# schematic.net
KiCad netlist of a schematic drawn in Altium Designer
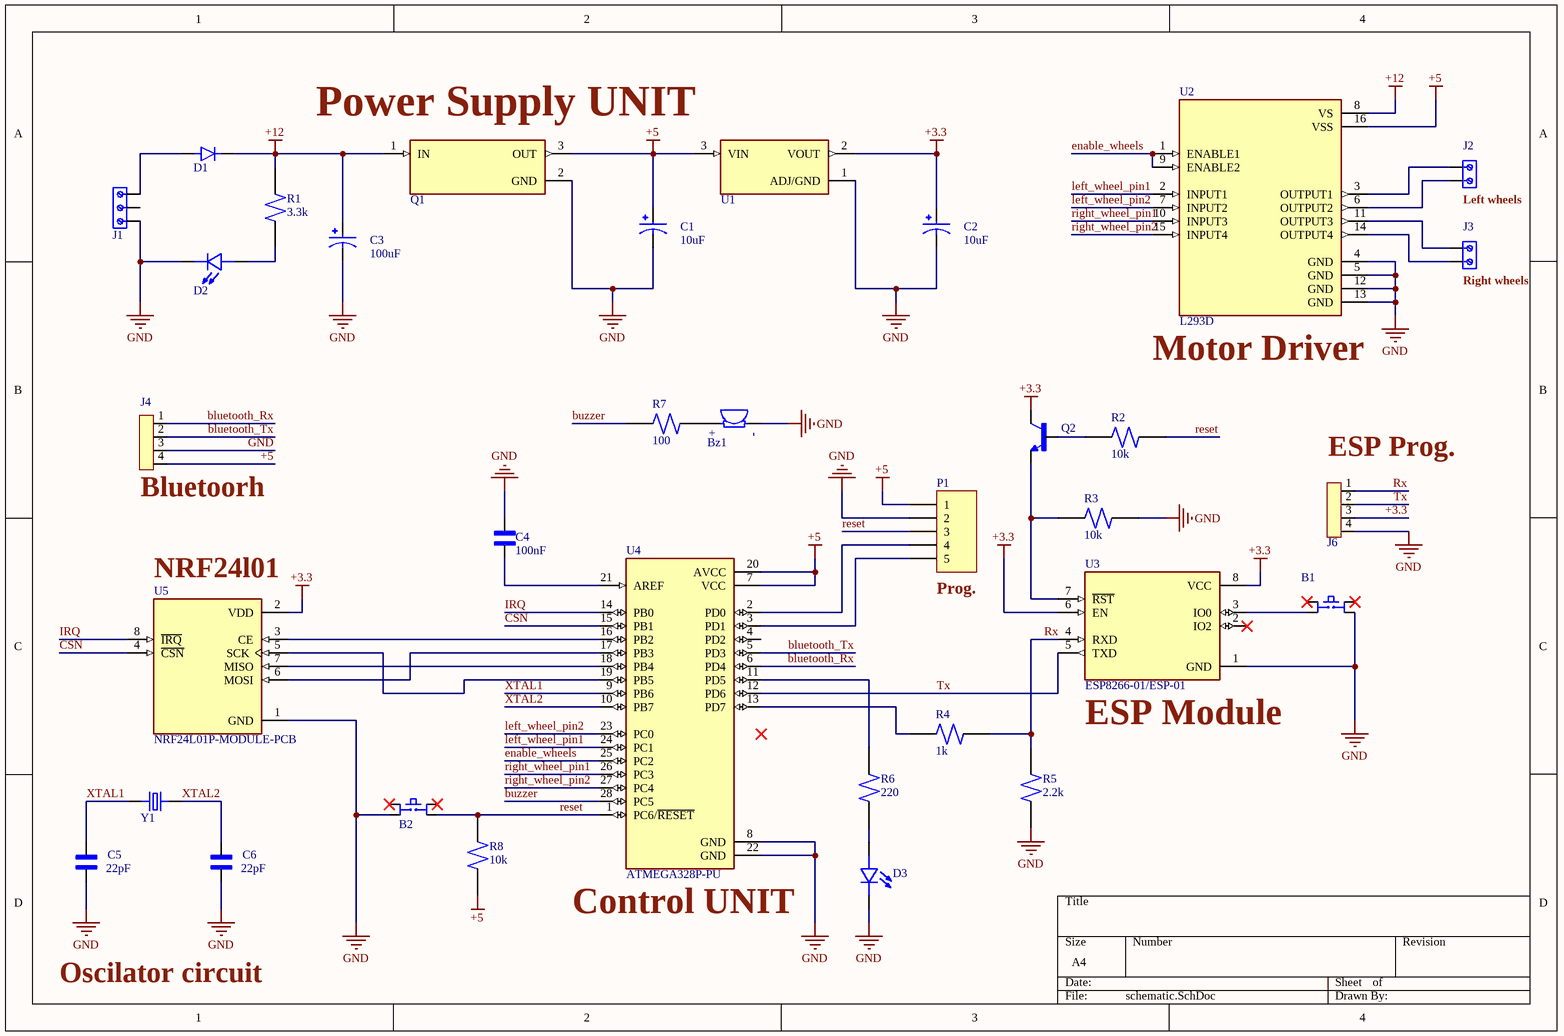
[diagram p0: schematic.SchDoc]

(export (version "E")
  (design (tool "Eeschema 10.0.6"))
  (components
    (comp (ref "B1")
      (value "Push button")
      (footprint "SW_TS02-66-95-BK-260-LCR-D")
      (libsource (lib "Installed library") (part "Push button"))
    )
    (comp (ref "B2")
      (value "Push button")
      (footprint "SW_TS02-66-95-BK-260-LCR-D")
      (libsource (lib "Installed library") (part "Push button"))
    )
    (comp (ref "Bz1")
      (value "AI-1223-TWT-12V-R")
      (footprint "XDCR_AI-1223-TWT-12V-R")
      (description "ELECTRO-MECHANICAL AUDIO INDICATOR")
      (fields (field (name "MF") "PUI Audio,"))
      (libsource (lib "Installed library") (part "Buzzer"))
    )
    (comp (ref "C1")
      (value "10uF")
      (footprint "CAPPRD500W50D500H1100")
      (description "FS-A")
      (fields (field (name "MF") "{'manufacturer': u'Panasonic'}") (field (name "MP") "EEUFS0J221B"))
      (libsource (lib "Installed library") (part "Electrolytic capacitor"))
    )
    (comp (ref "C2")
      (value "10uF")
      (footprint "CAPPRD500W50D500H1100")
      (description "FS-A")
      (fields (field (name "MF") "{'manufacturer': u'Panasonic'}") (field (name "MP") "EEUFS0J221B"))
      (libsource (lib "Installed library") (part "Electrolytic capacitor"))
    )
    (comp (ref "C3")
      (value "100uF")
      (footprint "CAPPRD500W50D500H1100")
      (description "FS-A")
      (fields (field (name "MF") "{'manufacturer': u'Panasonic'}") (field (name "MP") "EEUFS0J221B"))
      (libsource (lib "Installed library") (part "Electrolytic capacitor"))
    )
    (comp (ref "C4")
      (value "100nF")
      (footprint "CAPRB500W50L450T300H550")
      (description "2200 pF Â±10% 250V Ceramic Capacitor X7R Radial")
      (fields (field (name "DIGI-KEY_PART_NUMBER") "445-173386-1-ND") (field (name "MF") "TDK"))
      (libsource (lib "Installed library") (part "Ceramic capacitor"))
    )
    (comp (ref "C5")
      (value "22pF")
      (footprint "CAPRB500W50L450T300H550")
      (description "2200 pF Â±10% 250V Ceramic Capacitor X7R Radial")
      (fields (field (name "DIGI-KEY_PART_NUMBER") "445-173386-1-ND") (field (name "MF") "TDK"))
      (libsource (lib "") (part "Ceramic capacitor_1"))
    )
    (comp (ref "C6")
      (value "22pF")
      (footprint "CAPRB500W50L450T300H550")
      (description "2200 pF Â±10% 250V Ceramic Capacitor X7R Radial")
      (fields (field (name "DIGI-KEY_PART_NUMBER") "445-173386-1-ND") (field (name "MF") "TDK"))
      (libsource (lib "") (part "Ceramic capacitor_1"))
    )
    (comp (ref "D1")
      (value "1N4007")
      (footprint "DIOAD1060W70L435D230")
      (description "Diode Switching 1KV 1A 2-Pin DO-41")
      (libsource (lib "Installed library") (part "Diode"))
    )
    (comp (ref "D2")
      (value "L08R5000Q1")
      (footprint "LEDRD254W57D500H1070")
      (description "LED, Orange, Through Hole, T-1 3/4 (5mm), 30 mA, 2.1 V, 635 nm")
      (fields (field (name "MF") "{'manufacturer': u'LED Technology'}"))
      (libsource (lib "Installed library") (part "LED"))
    )
    (comp (ref "D3")
      (value "L08R5000Q1")
      (footprint "LEDRD254W57D500H1070")
      (description "LED, Orange, Through Hole, T-1 3/4 (5mm), 30 mA, 2.1 V, 635 nm")
      (fields (field (name "MF") "{'manufacturer': u'LED Technology'}"))
      (libsource (lib "Installed library") (part "LED"))
    )
    (comp (ref "J1")
      (value "691214110003")
      (footprint "691214110003")
      (description "3 Position Wire to Board Terminal Block Horizontal with Board 0.138 (3.50mm) Through Hole")
      (fields (field (name "MF") "Wurth Elektronik"))
      (libsource (lib "Installed library") (part "Terminal blocks - 3Pins (Small)"))
    )
    (comp (ref "J2")
      (value "691111710002")
      (footprint "691111710002")
      (description "2 Position Wire to Board Terminal Block Horizontal with Board 0.197 _5.00mm_ Through Hole")
      (fields (field (name "MF") "Wurth Electronics"))
      (libsource (lib "Installed library") (part "Terminal Block - 2Pins"))
    )
    (comp (ref "J3")
      (value "691111710002")
      (footprint "691111710002")
      (description "2 Position Wire to Board Terminal Block Horizontal with Board 0.197 _5.00mm_ Through Hole")
      (fields (field (name "MF") "Wurth Electronics"))
      (libsource (lib "Installed library") (part "Terminal Block - 2Pins"))
    )
    (comp (ref "J4")
      (value "PPTC041LFBN-RC")
      (footprint "SULLINS_PPTC041LFBN-RC")
      (description "4 Position Header Connector Through Hole")
      (fields (field (name "MF") "Sullins Connector"))
      (libsource (lib "Installed library") (part "Female header - 4Pins"))
    )
    (comp (ref "J6")
      (value "PPTC041LFBN-RC")
      (footprint "SULLINS_PPTC041LFBN-RC")
      (description "4 Position Header Connector Through Hole")
      (fields (field (name "MF") "Sullins Connector"))
      (libsource (lib "Installed library") (part "Female header - 4Pins"))
    )
    (comp (ref "P1")
      (value "Header 5")
      (footprint "HDR1X5")
      (description "Header, 5-Pin")
      (fields (field (name "PUBLISHER") "Altium Limited"))
      (libsource (lib "Miscellaneous Connectors") (part "Header 5"))
    )
    (comp (ref "Q1")
      (value "5V Regulator")
      (footprint "TO254P1054X470X1955-3")
      (fields (field (name "MP") "LM7805CT/NOPB"))
      (libsource (lib "Installed library") (part "LM7805"))
    )
    (comp (ref "Q2")
      (value "BJT Transistor")
      (footprint "TO92250P510H770-3")
      (fields (field (name "MP") "BC547B"))
      (libsource (lib "Installed library") (part "BC547B"))
    )
    (comp (ref "R1")
      (value "3.3k")
      (footprint "RESAD1100W55L680D260")
      (description "(MFR-25FBF52-10K) 10,2 kOhm bei 1% 0,25W, 1/4W Durchbohrlochwiderstand Axial Metal Film")
      (fields (field (name "DIGI-KEY_PART_NUMBER") "10.2KXBK-ND") (field (name "MF") "Yageo"))
      (libsource (lib "Installed library") (part "Resistor (0.25W)"))
    )
    (comp (ref "R2")
      (value "10k")
      (footprint "RESAD1100W55L680D260")
      (description "(MFR-25FBF52-10K) 10,2 kOhm bei 1% 0,25W, 1/4W Durchbohrlochwiderstand Axial Metal Film")
      (fields (field (name "DIGI-KEY_PART_NUMBER") "10.2KXBK-ND") (field (name "MF") "Yageo"))
      (libsource (lib "Installed library") (part "Resistor (0.25W)"))
    )
    (comp (ref "R3")
      (value "10k")
      (footprint "RESAD1100W55L680D260")
      (description "(MFR-25FBF52-10K) 10,2 kOhm bei 1% 0,25W, 1/4W Durchbohrlochwiderstand Axial Metal Film")
      (fields (field (name "DIGI-KEY_PART_NUMBER") "10.2KXBK-ND") (field (name "MF") "Yageo"))
      (libsource (lib "Installed library") (part "Resistor (0.25W)"))
    )
    (comp (ref "R4")
      (value "1k")
      (footprint "RESAD1100W55L680D260")
      (description "(MFR-25FBF52-10K) 10,2 kOhm bei 1% 0,25W, 1/4W Durchbohrlochwiderstand Axial Metal Film")
      (fields (field (name "DIGI-KEY_PART_NUMBER") "10.2KXBK-ND") (field (name "MF") "Yageo"))
      (libsource (lib "Installed library") (part "Resistor (0.25W)"))
    )
    (comp (ref "R5")
      (value "2.2k")
      (footprint "RESAD1100W55L680D260")
      (description "(MFR-25FBF52-10K) 10,2 kOhm bei 1% 0,25W, 1/4W Durchbohrlochwiderstand Axial Metal Film")
      (fields (field (name "DIGI-KEY_PART_NUMBER") "10.2KXBK-ND") (field (name "MF") "Yageo"))
      (libsource (lib "Installed library") (part "Resistor (0.25W)"))
    )
    (comp (ref "R6")
      (value "220")
      (footprint "RESAD1100W55L680D260")
      (description "(MFR-25FBF52-10K) 10,2 kOhm bei 1% 0,25W, 1/4W Durchbohrlochwiderstand Axial Metal Film")
      (fields (field (name "DIGI-KEY_PART_NUMBER") "10.2KXBK-ND") (field (name "MF") "Yageo"))
      (libsource (lib "Installed library") (part "Resistor (0.25W)"))
    )
    (comp (ref "R7")
      (value "100")
      (footprint "RESAD1100W55L680D260")
      (description "(MFR-25FBF52-10K) 10,2 kOhm bei 1% 0,25W, 1/4W Durchbohrlochwiderstand Axial Metal Film")
      (fields (field (name "DIGI-KEY_PART_NUMBER") "10.2KXBK-ND") (field (name "MF") "Yageo"))
      (libsource (lib "Installed library") (part "Resistor (0.25W)"))
    )
    (comp (ref "R8")
      (value "10k")
      (footprint "RESAD1100W55L680D260")
      (description "(MFR-25FBF52-10K) 10,2 kOhm bei 1% 0,25W, 1/4W Durchbohrlochwiderstand Axial Metal Film")
      (fields (field (name "DIGI-KEY_PART_NUMBER") "10.2KXBK-ND") (field (name "MF") "Yageo"))
      (libsource (lib "Installed library") (part "Resistor (0.25W)"))
    )
    (comp (ref "U1")
      (value "3.3V Regulator")
      (footprint "TO255P1020X450X1968-3")
      (fields (field (name "MP") "LD1117V33"))
      (libsource (lib "Installed library") (part "LD1117V33"))
    )
    (comp (ref "U2")
      (value "L293D")
      (footprint "DIP880W50P254L2000H510Q16")
      (description "4-Channel Motor Driver 24V 16-Pin Power PDIP Tube")
      (libsource (lib "Installed library") (part "L293D"))
    )
    (comp (ref "U3")
      (value "ESP8266-01/ESP-01")
      (footprint "XCVR_ESP8266-01/ESP-01")
      (libsource (lib "Installed library") (part "ESP8266-01 Module"))
    )
    (comp (ref "U4")
      (value "ATMEGA328P-PU")
      (footprint "DIP794W46P254L2967H457Q28B")
      (description "ATmega Series 20 MHz 32 KB Flash 2 KB SRAM 8-Bit Microcontroller - DIP-28")
      (libsource (lib "Installed library") (part "ATMEGA328P-PU"))
    )
    (comp (ref "U5")
      (value "NRF24L01P-MODULE-PCB")
      (footprint "XCVR_NRF24L01P-MODULE-PCB")
      (description "- Transceiver For Use With nRF24L01+")
      (fields (field (name "MF") "Nordic Semiconductor"))
      (libsource (lib "NRF24L01P-MODULE-PCB") (part "NRF24L01P-MODULE-PCB"))
    )
    (comp (ref "Y1")
      (value "ECS-160-S-4")
      (footprint "XTAL_ECS-160-20-4X")
      (description "CRYSTAL T/H")
      (fields (field (name "MF") "{'manufacturer': u'ECS Inc.'}"))
      (libsource (lib "Installed library") (part "Crystal oscilator"))
    )
  )
  (nets
    (net (code "1") (name "+3.3") (class "Default")
      (node (ref "C2") (pin "P") (pinfunction "P_P") (pintype "passive"))
      (node (ref "J6") (pin "3") (pinfunction "3_3") (pintype "passive"))
      (node (ref "Q2") (pin "1") (pinfunction "C_1") (pintype "passive"))
      (node (ref "U1") (pin "2") (pinfunction "VOUT_2") (pintype "output"))
      (node (ref "U3") (pin "6") (pinfunction "EN_6") (pintype "input"))
      (node (ref "U3") (pin "8") (pinfunction "VCC_8") (pintype "power_in"))
      (node (ref "U5") (pin "2") (pinfunction "VDD_2") (pintype "power_in"))
    )
    (net (code "2") (name "+5") (class "Default")
      (node (ref "C1") (pin "P") (pinfunction "P_P") (pintype "passive"))
      (node (ref "J4") (pin "4") (pinfunction "4_4") (pintype "passive"))
      (node (ref "P1") (pin "1") (pinfunction "1_1") (pintype "passive"))
      (node (ref "Q1") (pin "3") (pinfunction "OUT_3") (pintype "output"))
      (node (ref "R8") (pin "1") (pinfunction "1_1") (pintype "passive"))
      (node (ref "U1") (pin "3") (pinfunction "VIN_3") (pintype "input"))
      (node (ref "U2") (pin "16") (pinfunction "VSS_16") (pintype "power_in"))
      (node (ref "U4") (pin "20") (pinfunction "AVCC_20") (pintype "power_in"))
      (node (ref "U4") (pin "7") (pinfunction "VCC_7") (pintype "power_in"))
    )
    (net (code "3") (name "+12") (class "Default")
      (node (ref "C3") (pin "P") (pinfunction "P_P") (pintype "passive"))
      (node (ref "D1") (pin "C") (pinfunction "C_C") (pintype "passive"))
      (node (ref "Q1") (pin "1") (pinfunction "IN_1") (pintype "input"))
      (node (ref "R1") (pin "2") (pinfunction "2_2") (pintype "passive"))
      (node (ref "U2") (pin "8") (pinfunction "VS_8") (pintype "power_in"))
    )
    (net (code "4") (name "/CSN") (class "Default")
      (node (ref "U4") (pin "15") (pinfunction "PB1_15") (pintype "bidirectional"))
      (node (ref "U5") (pin "4") (pinfunction "~{CSN}_4") (pintype "input"))
    )
    (net (code "5") (name "/IRQ") (class "Default")
      (node (ref "U4") (pin "14") (pinfunction "PB0_14") (pintype "bidirectional"))
      (node (ref "U5") (pin "8") (pinfunction "~{IRQ}_8") (pintype "input"))
    )
    (net (code "6") (name "/Rx") (class "Default")
      (node (ref "J6") (pin "1") (pinfunction "1_1") (pintype "passive"))
      (node (ref "R4") (pin "1") (pinfunction "1_1") (pintype "passive"))
      (node (ref "R5") (pin "2") (pinfunction "2_2") (pintype "passive"))
      (node (ref "U3") (pin "4") (pinfunction "RXD_4") (pintype "input"))
    )
    (net (code "7") (name "/Tx") (class "Default")
      (node (ref "J6") (pin "2") (pinfunction "2_2") (pintype "passive"))
      (node (ref "U3") (pin "5") (pinfunction "TXD_5") (pintype "output"))
      (node (ref "U4") (pin "12") (pinfunction "PD6_12") (pintype "bidirectional"))
    )
    (net (code "8") (name "/XTAL1") (class "Default")
      (node (ref "C5") (pin "2") (pinfunction "2_2") (pintype "passive"))
      (node (ref "U4") (pin "9") (pinfunction "PB6_9") (pintype "bidirectional"))
      (node (ref "Y1") (pin "1") (pinfunction "1_1") (pintype "passive"))
    )
    (net (code "9") (name "/XTAL2") (class "Default")
      (node (ref "C6") (pin "2") (pinfunction "2_2") (pintype "passive"))
      (node (ref "U4") (pin "10") (pinfunction "PB7_10") (pintype "bidirectional"))
      (node (ref "Y1") (pin "2") (pinfunction "2_2") (pintype "passive"))
    )
    (net (code "10") (name "/bluetooth_Rx") (class "Default")
      (node (ref "J4") (pin "1") (pinfunction "1_1") (pintype "passive"))
      (node (ref "U4") (pin "6") (pinfunction "PD4_6") (pintype "bidirectional"))
    )
    (net (code "11") (name "/bluetooth_Tx") (class "Default")
      (node (ref "J4") (pin "2") (pinfunction "2_2") (pintype "passive"))
      (node (ref "U4") (pin "5") (pinfunction "PD3_5") (pintype "bidirectional"))
    )
    (net (code "12") (name "/buzzer") (class "Default")
      (node (ref "R7") (pin "1") (pinfunction "1_1") (pintype "passive"))
      (node (ref "U4") (pin "28") (pinfunction "PC5_28") (pintype "bidirectional"))
    )
    (net (code "13") (name "/enable_wheels") (class "Default")
      (node (ref "U2") (pin "1") (pinfunction "ENABLE1_1") (pintype "input"))
      (node (ref "U2") (pin "9") (pinfunction "ENABLE2_9") (pintype "input"))
      (node (ref "U4") (pin "25") (pinfunction "PC2_25") (pintype "bidirectional"))
    )
    (net (code "14") (name "/left_wheel_pin1") (class "Default")
      (node (ref "U2") (pin "2") (pinfunction "INPUT1_2") (pintype "input"))
      (node (ref "U4") (pin "24") (pinfunction "PC1_24") (pintype "bidirectional"))
    )
    (net (code "15") (name "/left_wheel_pin2") (class "Default")
      (node (ref "U2") (pin "7") (pinfunction "INPUT2_7") (pintype "input"))
      (node (ref "U4") (pin "23") (pinfunction "PC0_23") (pintype "bidirectional"))
    )
    (net (code "16") (name "/reset") (class "Default")
      (node (ref "B2") (pin "4") (pinfunction "4_4") (pintype "passive"))
      (node (ref "P1") (pin "3") (pinfunction "3_3") (pintype "passive"))
      (node (ref "R2") (pin "2") (pinfunction "2_2") (pintype "passive"))
      (node (ref "R8") (pin "2") (pinfunction "2_2") (pintype "passive"))
      (node (ref "U4") (pin "1") (pinfunction "PC6/~{RESET}_1") (pintype "bidirectional"))
    )
    (net (code "17") (name "/right_wheel_pin1") (class "Default")
      (node (ref "U2") (pin "10") (pinfunction "INPUT3_10") (pintype "input"))
      (node (ref "U4") (pin "26") (pinfunction "PC3_26") (pintype "bidirectional"))
    )
    (net (code "18") (name "/right_wheel_pin2") (class "Default")
      (node (ref "U2") (pin "15") (pinfunction "INPUT4_15") (pintype "input"))
      (node (ref "U4") (pin "27") (pinfunction "PC4_27") (pintype "bidirectional"))
    )
    (net (code "19") (name "GND") (class "Default")
      (node (ref "B1") (pin "4") (pinfunction "4_4") (pintype "passive"))
      (node (ref "B2") (pin "2") (pinfunction "2_2") (pintype "passive"))
      (node (ref "Bz1") (pin "N") (pinfunction "NEG_N") (pintype "passive"))
      (node (ref "C1") (pin "N") (pinfunction "N_N") (pintype "passive"))
      (node (ref "C2") (pin "N") (pinfunction "N_N") (pintype "passive"))
      (node (ref "C3") (pin "N") (pinfunction "N_N") (pintype "passive"))
      (node (ref "C4") (pin "1") (pinfunction "1_1") (pintype "passive"))
      (node (ref "C5") (pin "1") (pinfunction "1_1") (pintype "passive"))
      (node (ref "C6") (pin "1") (pinfunction "1_1") (pintype "passive"))
      (node (ref "D2") (pin "C") (pinfunction "C_C") (pintype "passive"))
      (node (ref "D3") (pin "C") (pinfunction "C_C") (pintype "passive"))
      (node (ref "J1") (pin "1") (pinfunction "1_1") (pintype "passive"))
      (node (ref "J4") (pin "3") (pinfunction "3_3") (pintype "passive"))
      (node (ref "J6") (pin "4") (pinfunction "4_4") (pintype "passive"))
      (node (ref "P1") (pin "2") (pinfunction "2_2") (pintype "passive"))
      (node (ref "Q1") (pin "2") (pinfunction "GND_2") (pintype "power_in"))
      (node (ref "R3") (pin "2") (pinfunction "2_2") (pintype "passive"))
      (node (ref "R5") (pin "1") (pinfunction "1_1") (pintype "passive"))
      (node (ref "U1") (pin "1") (pinfunction "ADJ/GND_1") (pintype "passive"))
      (node (ref "U2") (pin "12") (pinfunction "GND_12") (pintype "power_in"))
      (node (ref "U2") (pin "13") (pinfunction "GND_13") (pintype "power_in"))
      (node (ref "U2") (pin "4") (pinfunction "GND_4") (pintype "power_in"))
      (node (ref "U2") (pin "5") (pinfunction "GND_5") (pintype "power_in"))
      (node (ref "U3") (pin "1") (pinfunction "GND_1") (pintype "power_in"))
      (node (ref "U4") (pin "22") (pinfunction "GND_22") (pintype "power_in"))
      (node (ref "U4") (pin "8") (pinfunction "GND_8") (pintype "power_in"))
      (node (ref "U5") (pin "1") (pinfunction "GND_1") (pintype "power_in"))
    )
    (net (code "20") (name "Net-(Bz1-POS)") (class "Default")
      (node (ref "Bz1") (pin "P") (pinfunction "POS_P") (pintype "passive"))
      (node (ref "R7") (pin "2") (pinfunction "2_2") (pintype "passive"))
    )
    (net (code "21") (name "Net-(D1-PadA)") (class "Default")
      (node (ref "D1") (pin "A") (pinfunction "A_A") (pintype "passive"))
      (node (ref "J1") (pin "3") (pinfunction "3_3") (pintype "passive"))
    )
    (net (code "22") (name "Net-(D2-PadA)") (class "Default")
      (node (ref "D2") (pin "A") (pinfunction "A_A") (pintype "passive"))
      (node (ref "R1") (pin "1") (pinfunction "1_1") (pintype "passive"))
    )
    (net (code "23") (name "Net-(D3-PadA)") (class "Default")
      (node (ref "D3") (pin "A") (pinfunction "A_A") (pintype "passive"))
      (node (ref "R6") (pin "2") (pinfunction "2_2") (pintype "passive"))
    )
    (net (code "24") (name "Net-(Q2-B)") (class "Default")
      (node (ref "Q2") (pin "2") (pinfunction "B_2") (pintype "passive"))
      (node (ref "R2") (pin "1") (pinfunction "1_1") (pintype "passive"))
    )
    (net (code "25") (name "Net-(Q2-E)") (class "Default")
      (node (ref "Q2") (pin "3") (pinfunction "E_3") (pintype "passive"))
      (node (ref "R3") (pin "1") (pinfunction "1_1") (pintype "passive"))
      (node (ref "U3") (pin "7") (pinfunction "~{RST}_7") (pintype "input"))
    )
    (net (code "26") (name "Net-(U2-OUTPUT1)") (class "Default")
      (node (ref "J2") (pin "1") (pinfunction "1_1") (pintype "passive"))
      (node (ref "U2") (pin "3") (pinfunction "OUTPUT1_3") (pintype "output"))
    )
    (net (code "27") (name "Net-(U2-OUTPUT2)") (class "Default")
      (node (ref "J2") (pin "2") (pinfunction "2_2") (pintype "passive"))
      (node (ref "U2") (pin "6") (pinfunction "OUTPUT2_6") (pintype "output"))
    )
    (net (code "28") (name "Net-(U2-OUTPUT3)") (class "Default")
      (node (ref "J3") (pin "1") (pinfunction "1_1") (pintype "passive"))
      (node (ref "U2") (pin "11") (pinfunction "OUTPUT3_11") (pintype "output"))
    )
    (net (code "29") (name "Net-(U2-OUTPUT4)") (class "Default")
      (node (ref "J3") (pin "2") (pinfunction "2_2") (pintype "passive"))
      (node (ref "U2") (pin "14") (pinfunction "OUTPUT4_14") (pintype "output"))
    )
    (net (code "30") (name "Net-(U3-IO0)") (class "Default")
      (node (ref "B1") (pin "2") (pinfunction "2_2") (pintype "passive"))
      (node (ref "U3") (pin "3") (pinfunction "IO0_3") (pintype "bidirectional"))
    )
    (net (code "31") (name "Net-(U4-AREF)") (class "Default")
      (node (ref "C4") (pin "2") (pinfunction "2_2") (pintype "passive"))
      (node (ref "U4") (pin "21") (pinfunction "AREF_21") (pintype "input"))
    )
    (net (code "32") (name "Net-(U4-PB2)") (class "Default")
      (node (ref "U4") (pin "16") (pinfunction "PB2_16") (pintype "bidirectional"))
      (node (ref "U5") (pin "3") (pinfunction "CE_3") (pintype "input"))
    )
    (net (code "33") (name "Net-(U4-PB3)") (class "Default")
      (node (ref "U4") (pin "17") (pinfunction "PB3_17") (pintype "bidirectional"))
      (node (ref "U5") (pin "6") (pinfunction "MOSI_6") (pintype "input"))
    )
    (net (code "34") (name "Net-(U4-PB4)") (class "Default")
      (node (ref "U4") (pin "18") (pinfunction "PB4_18") (pintype "bidirectional"))
      (node (ref "U5") (pin "7") (pinfunction "MISO_7") (pintype "input"))
    )
    (net (code "35") (name "Net-(U4-PB5)") (class "Default")
      (node (ref "U4") (pin "19") (pinfunction "PB5_19") (pintype "bidirectional"))
      (node (ref "U5") (pin "5") (pinfunction "SCK_5") (pintype "input"))
    )
    (net (code "36") (name "Net-(U4-PD0)") (class "Default")
      (node (ref "P1") (pin "4") (pinfunction "4_4") (pintype "passive"))
      (node (ref "U4") (pin "2") (pinfunction "PD0_2") (pintype "bidirectional"))
    )
    (net (code "37") (name "Net-(U4-PD1)") (class "Default")
      (node (ref "P1") (pin "5") (pinfunction "5_5") (pintype "passive"))
      (node (ref "U4") (pin "3") (pinfunction "PD1_3") (pintype "bidirectional"))
    )
    (net (code "38") (name "Net-(U4-PD5)") (class "Default")
      (node (ref "R6") (pin "1") (pinfunction "1_1") (pintype "passive"))
      (node (ref "U4") (pin "11") (pinfunction "PD5_11") (pintype "bidirectional"))
    )
    (net (code "39") (name "Net-(U4-PD7)") (class "Default")
      (node (ref "R4") (pin "2") (pinfunction "2_2") (pintype "passive"))
      (node (ref "U4") (pin "13") (pinfunction "PD7_13") (pintype "bidirectional"))
    )
    (net (code "40") (name "unconnected-(B1-Pad1)") (class "Default")
      (node (ref "B1") (pin "1") (pinfunction "1_1") (pintype "passive+no_connect"))
    )
    (net (code "41") (name "unconnected-(B1-Pad3)") (class "Default")
      (node (ref "B1") (pin "3") (pinfunction "3_3") (pintype "passive+no_connect"))
    )
    (net (code "42") (name "unconnected-(B2-Pad1)") (class "Default")
      (node (ref "B2") (pin "1") (pinfunction "1_1") (pintype "passive+no_connect"))
    )
    (net (code "43") (name "unconnected-(B2-Pad3)") (class "Default")
      (node (ref "B2") (pin "3") (pinfunction "3_3") (pintype "passive+no_connect"))
    )
    (net (code "44") (name "unconnected-(J1-Pad2)") (class "Default")
      (node (ref "J1") (pin "2") (pinfunction "2_2") (pintype "passive"))
    )
    (net (code "45") (name "unconnected-(U3-IO2-Pad2)") (class "Default")
      (node (ref "U3") (pin "2") (pinfunction "IO2_2") (pintype "bidirectional+no_connect"))
    )
    (net (code "46") (name "unconnected-(U4-PD2-Pad4)") (class "Default")
      (node (ref "U4") (pin "4") (pinfunction "PD2_4") (pintype "bidirectional"))
    )
  )
)
